# PGTN021_octasource2c_controls.net
KiCad netlist of a schematic drawn in EAGLE
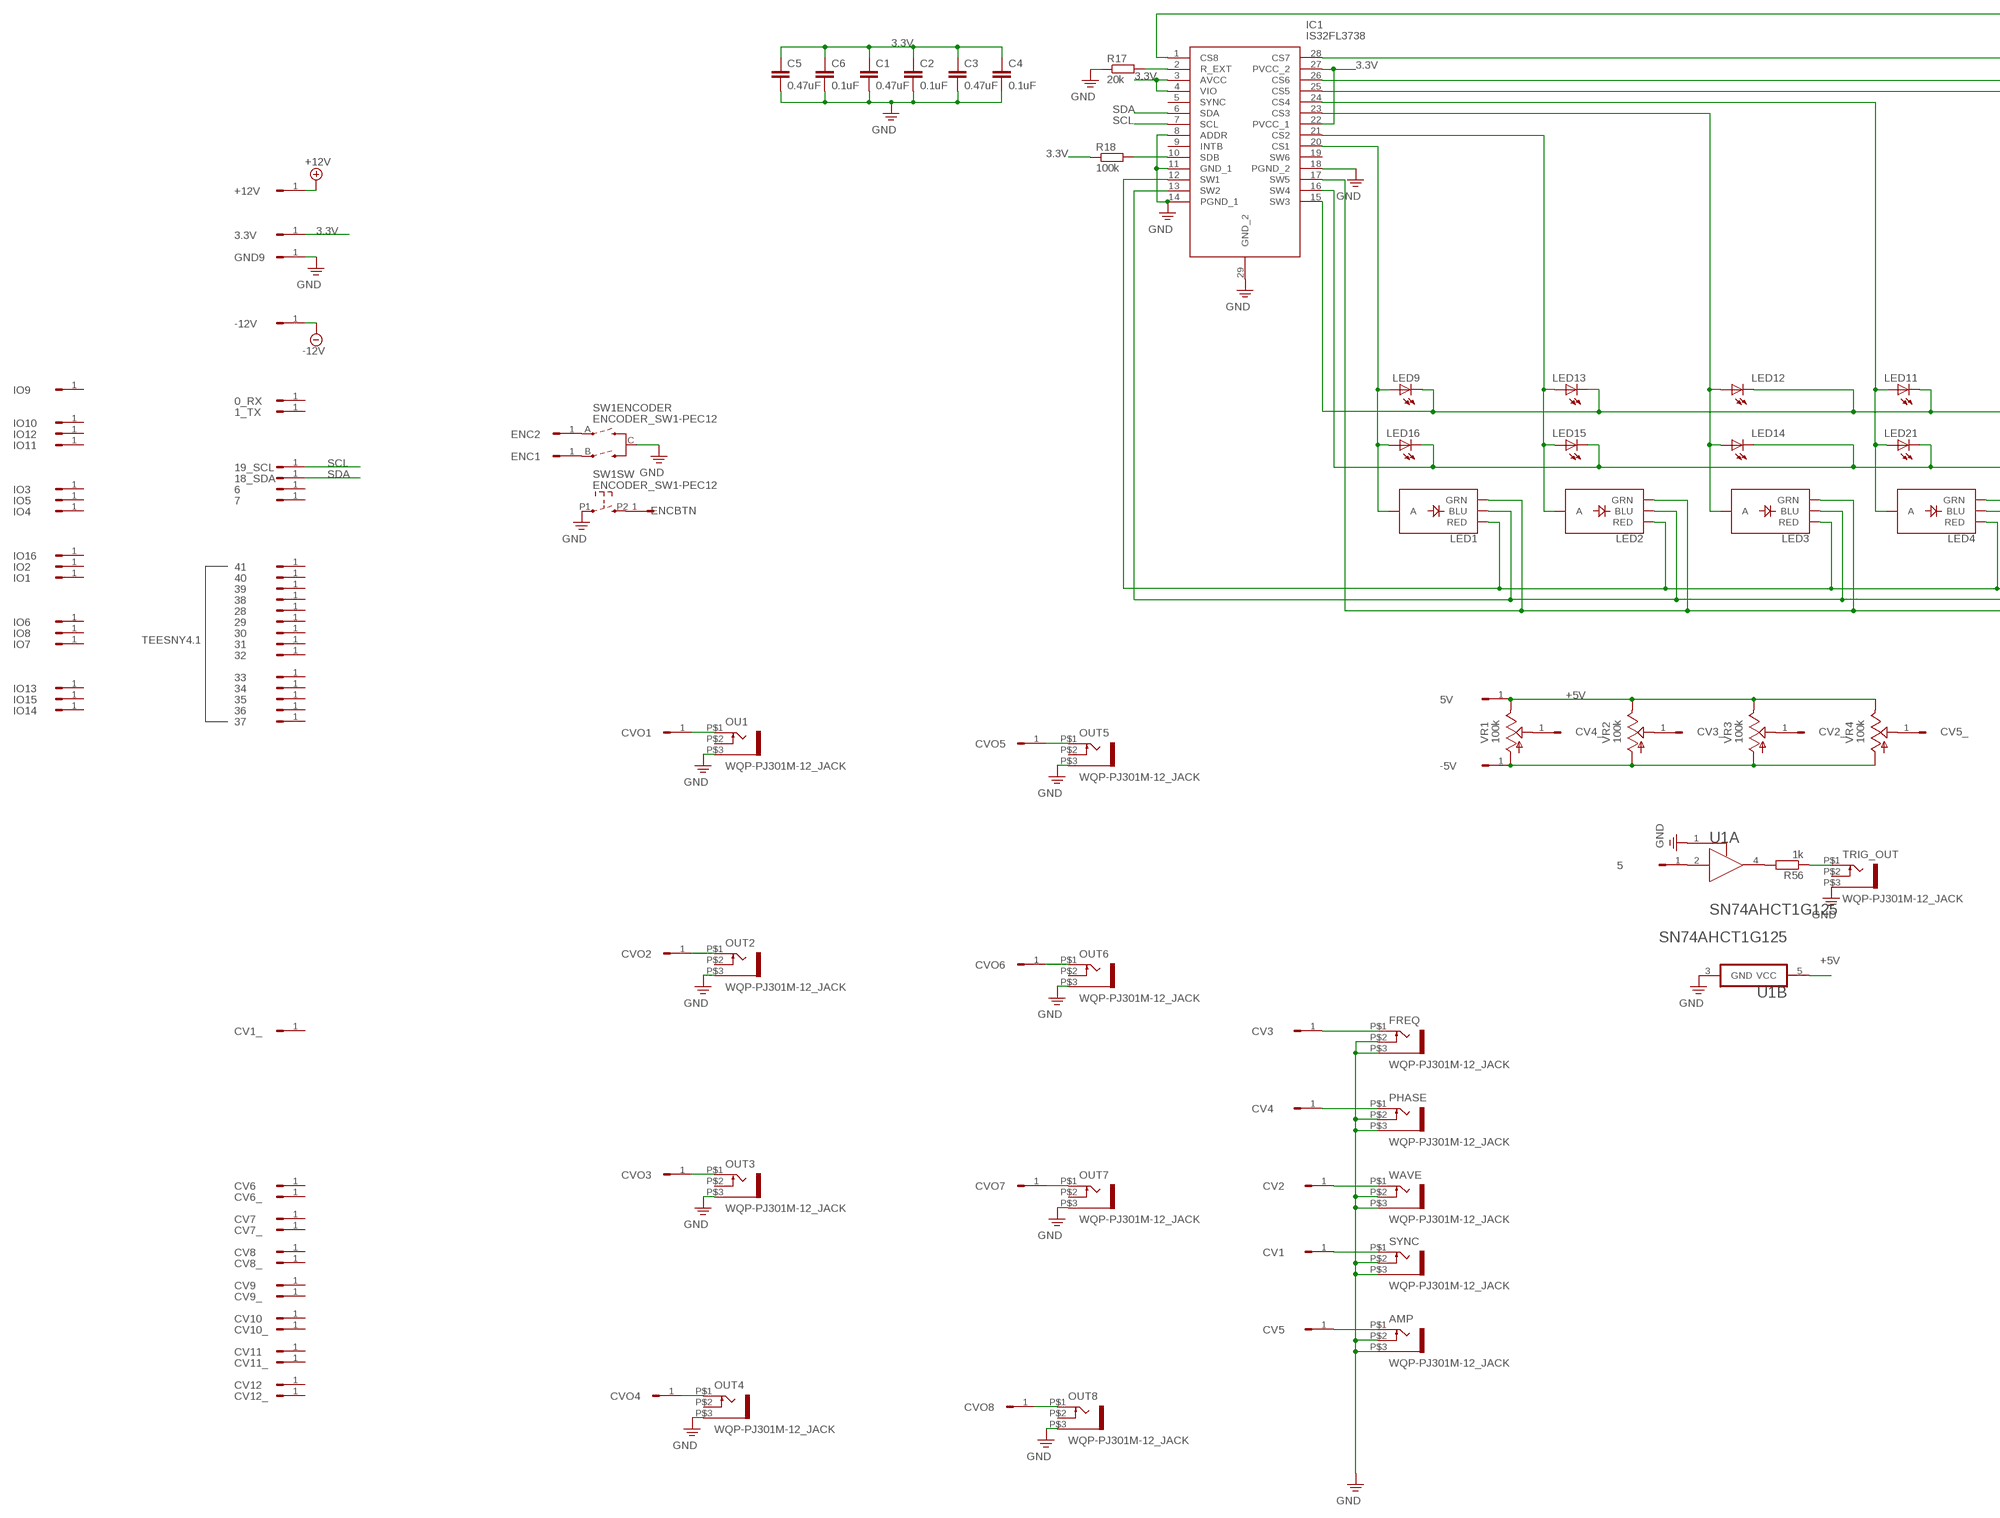
[diagram p0: schematic, sheet 1, part 1 of 2]
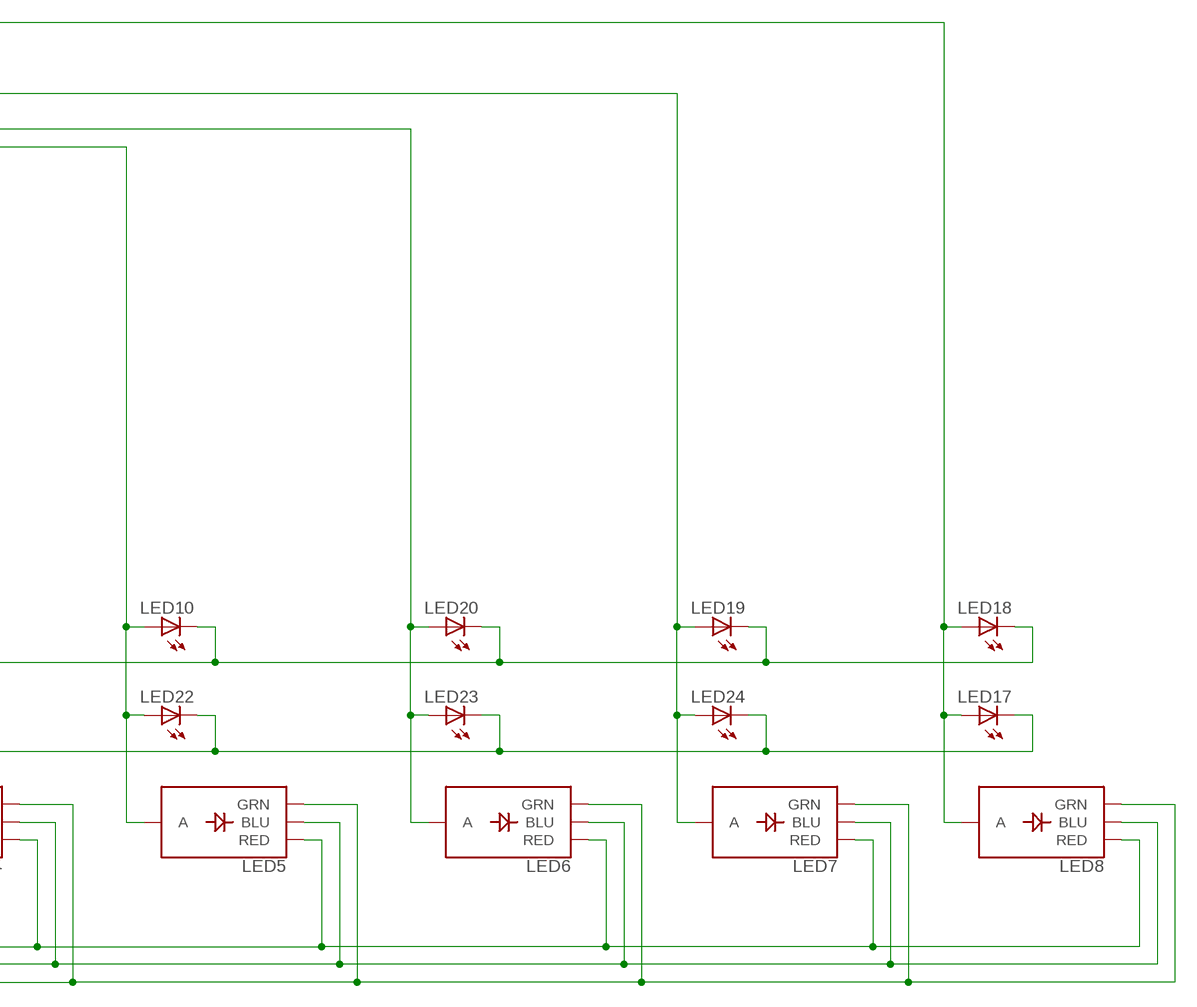
[diagram p1: schematic, sheet 1, part 2 of 2]

(export (version "E")
  (design (tool "Eeschema 10.0.6"))
  (components
    (comp (ref "+12V")
      (value "HEADER/MALE/01")
      (footprint "eagle-import:HEADER_MALE_01")
      (fields (field (name "SPICEPREFIX") "X"))
      (libsource (lib "eagle-import") (part "HEADER/MALE/01"))
    )
    (comp (ref "-5V")
      (value "HEADER/MALE/01")
      (footprint "eagle-import:HEADER_MALE_01")
      (fields (field (name "SPICEPREFIX") "X"))
      (libsource (lib "eagle-import") (part "HEADER/MALE/01"))
    )
    (comp (ref "-12V")
      (value "HEADER/MALE/01")
      (footprint "eagle-import:HEADER_MALE_01")
      (fields (field (name "SPICEPREFIX") "X"))
      (libsource (lib "eagle-import") (part "HEADER/MALE/01"))
    )
    (comp (ref "0_RX")
      (value "HEADER/MALE/01")
      (footprint "eagle-import:HEADER_MALE_01")
      (fields (field (name "SPICEPREFIX") "X"))
      (libsource (lib "eagle-import") (part "HEADER/MALE/01"))
    )
    (comp (ref "1_TX")
      (value "HEADER/MALE/01")
      (footprint "eagle-import:HEADER_MALE_01")
      (fields (field (name "SPICEPREFIX") "X"))
      (libsource (lib "eagle-import") (part "HEADER/MALE/01"))
    )
    (comp (ref "3.3V")
      (value "HEADER/MALE/01")
      (footprint "eagle-import:HEADER_MALE_01")
      (fields (field (name "SPICEPREFIX") "X"))
      (libsource (lib "eagle-import") (part "HEADER/MALE/01"))
    )
    (comp (ref "5")
      (value "HEADER/MALE/01")
      (footprint "eagle-import:HEADER_MALE_01")
      (fields (field (name "SPICEPREFIX") "X"))
      (libsource (lib "eagle-import") (part "HEADER/MALE/01"))
    )
    (comp (ref "5V")
      (value "HEADER/MALE/01")
      (footprint "eagle-import:HEADER_MALE_01")
      (fields (field (name "SPICEPREFIX") "X"))
      (libsource (lib "eagle-import") (part "HEADER/MALE/01"))
    )
    (comp (ref "6")
      (value "HEADER/MALE/01")
      (footprint "eagle-import:HEADER_MALE_01")
      (fields (field (name "SPICEPREFIX") "X"))
      (libsource (lib "eagle-import") (part "HEADER/MALE/01"))
    )
    (comp (ref "7")
      (value "HEADER/MALE/01")
      (footprint "eagle-import:HEADER_MALE_01")
      (fields (field (name "SPICEPREFIX") "X"))
      (libsource (lib "eagle-import") (part "HEADER/MALE/01"))
    )
    (comp (ref "18_SDA")
      (value "HEADER/MALE/01")
      (footprint "eagle-import:HEADER_MALE_01")
      (fields (field (name "SPICEPREFIX") "X"))
      (libsource (lib "eagle-import") (part "HEADER/MALE/01"))
    )
    (comp (ref "19_SCL")
      (value "HEADER/MALE/01")
      (footprint "eagle-import:HEADER_MALE_01")
      (fields (field (name "SPICEPREFIX") "X"))
      (libsource (lib "eagle-import") (part "HEADER/MALE/01"))
    )
    (comp (ref "28")
      (value "HEADER/MALE/01")
      (footprint "eagle-import:HEADER_MALE_01")
      (fields (field (name "SPICEPREFIX") "X"))
      (libsource (lib "eagle-import") (part "HEADER/MALE/01"))
    )
    (comp (ref "29")
      (value "HEADER/MALE/01")
      (footprint "eagle-import:HEADER_MALE_01")
      (fields (field (name "SPICEPREFIX") "X"))
      (libsource (lib "eagle-import") (part "HEADER/MALE/01"))
    )
    (comp (ref "30")
      (value "HEADER/MALE/01")
      (footprint "eagle-import:HEADER_MALE_01")
      (fields (field (name "SPICEPREFIX") "X"))
      (libsource (lib "eagle-import") (part "HEADER/MALE/01"))
    )
    (comp (ref "31")
      (value "HEADER/MALE/01")
      (footprint "eagle-import:HEADER_MALE_01")
      (fields (field (name "SPICEPREFIX") "X"))
      (libsource (lib "eagle-import") (part "HEADER/MALE/01"))
    )
    (comp (ref "32")
      (value "HEADER/MALE/01")
      (footprint "eagle-import:HEADER_MALE_01")
      (fields (field (name "SPICEPREFIX") "X"))
      (libsource (lib "eagle-import") (part "HEADER/MALE/01"))
    )
    (comp (ref "33")
      (value "HEADER/MALE/01")
      (footprint "eagle-import:HEADER_MALE_01")
      (fields (field (name "SPICEPREFIX") "X"))
      (libsource (lib "eagle-import") (part "HEADER/MALE/01"))
    )
    (comp (ref "34")
      (value "HEADER/MALE/01")
      (footprint "eagle-import:HEADER_MALE_01")
      (fields (field (name "SPICEPREFIX") "X"))
      (libsource (lib "eagle-import") (part "HEADER/MALE/01"))
    )
    (comp (ref "35")
      (value "HEADER/MALE/01")
      (footprint "eagle-import:HEADER_MALE_01")
      (fields (field (name "SPICEPREFIX") "X"))
      (libsource (lib "eagle-import") (part "HEADER/MALE/01"))
    )
    (comp (ref "36")
      (value "HEADER/MALE/01")
      (footprint "eagle-import:HEADER_MALE_01")
      (fields (field (name "SPICEPREFIX") "X"))
      (libsource (lib "eagle-import") (part "HEADER/MALE/01"))
    )
    (comp (ref "37")
      (value "HEADER/MALE/01")
      (footprint "eagle-import:HEADER_MALE_01")
      (fields (field (name "SPICEPREFIX") "X"))
      (libsource (lib "eagle-import") (part "HEADER/MALE/01"))
    )
    (comp (ref "38")
      (value "HEADER/MALE/01")
      (footprint "eagle-import:HEADER_MALE_01")
      (fields (field (name "SPICEPREFIX") "X"))
      (libsource (lib "eagle-import") (part "HEADER/MALE/01"))
    )
    (comp (ref "39")
      (value "HEADER/MALE/01")
      (footprint "eagle-import:HEADER_MALE_01")
      (fields (field (name "SPICEPREFIX") "X"))
      (libsource (lib "eagle-import") (part "HEADER/MALE/01"))
    )
    (comp (ref "40")
      (value "HEADER/MALE/01")
      (footprint "eagle-import:HEADER_MALE_01")
      (fields (field (name "SPICEPREFIX") "X"))
      (libsource (lib "eagle-import") (part "HEADER/MALE/01"))
    )
    (comp (ref "41")
      (value "HEADER/MALE/01")
      (footprint "eagle-import:HEADER_MALE_01")
      (fields (field (name "SPICEPREFIX") "X"))
      (libsource (lib "eagle-import") (part "HEADER/MALE/01"))
    )
    (comp (ref "AMP")
      (value "WQP-PJ301M-12_JACK")
      (footprint "eagle-import:WQP-PJ301M-12_JACK")
      (libsource (lib "eagle-import") (part "WQP-PJ301M-12_JACK"))
    )
    (comp (ref "C1")
      (value "0.47uF")
      (footprint "eagle-import:C0603")
      (libsource (lib "eagle-import") (part "CAPACITORC0603"))
    )
    (comp (ref "C2")
      (value "0.1uF")
      (footprint "eagle-import:C0603")
      (libsource (lib "eagle-import") (part "CAPACITORC0603"))
    )
    (comp (ref "C3")
      (value "0.47uF")
      (footprint "eagle-import:C0603")
      (libsource (lib "eagle-import") (part "CAPACITORC0603"))
    )
    (comp (ref "C4")
      (value "0.1uF")
      (footprint "eagle-import:C0603")
      (libsource (lib "eagle-import") (part "CAPACITORC0603"))
    )
    (comp (ref "C5")
      (value "0.47uF")
      (footprint "eagle-import:C0603")
      (libsource (lib "eagle-import") (part "CAPACITORC0603"))
    )
    (comp (ref "C6")
      (value "0.1uF")
      (footprint "eagle-import:C0603")
      (libsource (lib "eagle-import") (part "CAPACITORC0603"))
    )
    (comp (ref "CV1")
      (value "HEADER/MALE/01")
      (footprint "eagle-import:HEADER_MALE_01")
      (fields (field (name "SPICEPREFIX") "X"))
      (libsource (lib "eagle-import") (part "HEADER/MALE/01"))
    )
    (comp (ref "CV1_")
      (value "HEADER/MALE/01")
      (footprint "eagle-import:HEADER_MALE_01")
      (fields (field (name "SPICEPREFIX") "X"))
      (libsource (lib "eagle-import") (part "HEADER/MALE/01"))
    )
    (comp (ref "CV2")
      (value "HEADER/MALE/01")
      (footprint "eagle-import:HEADER_MALE_01")
      (fields (field (name "SPICEPREFIX") "X"))
      (libsource (lib "eagle-import") (part "HEADER/MALE/01"))
    )
    (comp (ref "CV2_")
      (value "HEADER/MALE/01")
      (footprint "eagle-import:HEADER_MALE_01")
      (fields (field (name "SPICEPREFIX") "X"))
      (libsource (lib "eagle-import") (part "HEADER/MALE/01"))
    )
    (comp (ref "CV3")
      (value "HEADER/MALE/01")
      (footprint "eagle-import:HEADER_MALE_01")
      (fields (field (name "SPICEPREFIX") "X"))
      (libsource (lib "eagle-import") (part "HEADER/MALE/01"))
    )
    (comp (ref "CV3_")
      (value "HEADER/MALE/01")
      (footprint "eagle-import:HEADER_MALE_01")
      (fields (field (name "SPICEPREFIX") "X"))
      (libsource (lib "eagle-import") (part "HEADER/MALE/01"))
    )
    (comp (ref "CV4")
      (value "HEADER/MALE/01")
      (footprint "eagle-import:HEADER_MALE_01")
      (fields (field (name "SPICEPREFIX") "X"))
      (libsource (lib "eagle-import") (part "HEADER/MALE/01"))
    )
    (comp (ref "CV4_")
      (value "HEADER/MALE/01")
      (footprint "eagle-import:HEADER_MALE_01")
      (fields (field (name "SPICEPREFIX") "X"))
      (libsource (lib "eagle-import") (part "HEADER/MALE/01"))
    )
    (comp (ref "CV5")
      (value "HEADER/MALE/01")
      (footprint "eagle-import:HEADER_MALE_01")
      (fields (field (name "SPICEPREFIX") "X"))
      (libsource (lib "eagle-import") (part "HEADER/MALE/01"))
    )
    (comp (ref "CV5_")
      (value "HEADER/MALE/01")
      (footprint "eagle-import:HEADER_MALE_01")
      (fields (field (name "SPICEPREFIX") "X"))
      (libsource (lib "eagle-import") (part "HEADER/MALE/01"))
    )
    (comp (ref "CV6")
      (value "HEADER/MALE/01")
      (footprint "eagle-import:HEADER_MALE_01")
      (fields (field (name "SPICEPREFIX") "X"))
      (libsource (lib "eagle-import") (part "HEADER/MALE/01"))
    )
    (comp (ref "CV6_")
      (value "HEADER/MALE/01")
      (footprint "eagle-import:HEADER_MALE_01")
      (fields (field (name "SPICEPREFIX") "X"))
      (libsource (lib "eagle-import") (part "HEADER/MALE/01"))
    )
    (comp (ref "CV7")
      (value "HEADER/MALE/01")
      (footprint "eagle-import:HEADER_MALE_01")
      (fields (field (name "SPICEPREFIX") "X"))
      (libsource (lib "eagle-import") (part "HEADER/MALE/01"))
    )
    (comp (ref "CV7_")
      (value "HEADER/MALE/01")
      (footprint "eagle-import:HEADER_MALE_01")
      (fields (field (name "SPICEPREFIX") "X"))
      (libsource (lib "eagle-import") (part "HEADER/MALE/01"))
    )
    (comp (ref "CV8")
      (value "HEADER/MALE/01")
      (footprint "eagle-import:HEADER_MALE_01")
      (fields (field (name "SPICEPREFIX") "X"))
      (libsource (lib "eagle-import") (part "HEADER/MALE/01"))
    )
    (comp (ref "CV8_")
      (value "HEADER/MALE/01")
      (footprint "eagle-import:HEADER_MALE_01")
      (fields (field (name "SPICEPREFIX") "X"))
      (libsource (lib "eagle-import") (part "HEADER/MALE/01"))
    )
    (comp (ref "CV9")
      (value "HEADER/MALE/01")
      (footprint "eagle-import:HEADER_MALE_01")
      (fields (field (name "SPICEPREFIX") "X"))
      (libsource (lib "eagle-import") (part "HEADER/MALE/01"))
    )
    (comp (ref "CV9_")
      (value "HEADER/MALE/01")
      (footprint "eagle-import:HEADER_MALE_01")
      (fields (field (name "SPICEPREFIX") "X"))
      (libsource (lib "eagle-import") (part "HEADER/MALE/01"))
    )
    (comp (ref "CV10")
      (value "HEADER/MALE/01")
      (footprint "eagle-import:HEADER_MALE_01")
      (fields (field (name "SPICEPREFIX") "X"))
      (libsource (lib "eagle-import") (part "HEADER/MALE/01"))
    )
    (comp (ref "CV10_")
      (value "HEADER/MALE/01")
      (footprint "eagle-import:HEADER_MALE_01")
      (fields (field (name "SPICEPREFIX") "X"))
      (libsource (lib "eagle-import") (part "HEADER/MALE/01"))
    )
    (comp (ref "CV11")
      (value "HEADER/MALE/01")
      (footprint "eagle-import:HEADER_MALE_01")
      (fields (field (name "SPICEPREFIX") "X"))
      (libsource (lib "eagle-import") (part "HEADER/MALE/01"))
    )
    (comp (ref "CV11_")
      (value "HEADER/MALE/01")
      (footprint "eagle-import:HEADER_MALE_01")
      (fields (field (name "SPICEPREFIX") "X"))
      (libsource (lib "eagle-import") (part "HEADER/MALE/01"))
    )
    (comp (ref "CV12")
      (value "HEADER/MALE/01")
      (footprint "eagle-import:HEADER_MALE_01")
      (fields (field (name "SPICEPREFIX") "X"))
      (libsource (lib "eagle-import") (part "HEADER/MALE/01"))
    )
    (comp (ref "CV12_")
      (value "HEADER/MALE/01")
      (footprint "eagle-import:HEADER_MALE_01")
      (fields (field (name "SPICEPREFIX") "X"))
      (libsource (lib "eagle-import") (part "HEADER/MALE/01"))
    )
    (comp (ref "CVO1")
      (value "HEADER/MALE/01")
      (footprint "eagle-import:HEADER_MALE_01")
      (fields (field (name "SPICEPREFIX") "X"))
      (libsource (lib "eagle-import") (part "HEADER/MALE/01"))
    )
    (comp (ref "CVO2")
      (value "HEADER/MALE/01")
      (footprint "eagle-import:HEADER_MALE_01")
      (fields (field (name "SPICEPREFIX") "X"))
      (libsource (lib "eagle-import") (part "HEADER/MALE/01"))
    )
    (comp (ref "CVO3")
      (value "HEADER/MALE/01")
      (footprint "eagle-import:HEADER_MALE_01")
      (fields (field (name "SPICEPREFIX") "X"))
      (libsource (lib "eagle-import") (part "HEADER/MALE/01"))
    )
    (comp (ref "CVO4")
      (value "HEADER/MALE/01")
      (footprint "eagle-import:HEADER_MALE_01")
      (fields (field (name "SPICEPREFIX") "X"))
      (libsource (lib "eagle-import") (part "HEADER/MALE/01"))
    )
    (comp (ref "CVO5")
      (value "HEADER/MALE/01")
      (footprint "eagle-import:HEADER_MALE_01")
      (fields (field (name "SPICEPREFIX") "X"))
      (libsource (lib "eagle-import") (part "HEADER/MALE/01"))
    )
    (comp (ref "CVO6")
      (value "HEADER/MALE/01")
      (footprint "eagle-import:HEADER_MALE_01")
      (fields (field (name "SPICEPREFIX") "X"))
      (libsource (lib "eagle-import") (part "HEADER/MALE/01"))
    )
    (comp (ref "CVO7")
      (value "HEADER/MALE/01")
      (footprint "eagle-import:HEADER_MALE_01")
      (fields (field (name "SPICEPREFIX") "X"))
      (libsource (lib "eagle-import") (part "HEADER/MALE/01"))
    )
    (comp (ref "CVO8")
      (value "HEADER/MALE/01")
      (footprint "eagle-import:HEADER_MALE_01")
      (fields (field (name "SPICEPREFIX") "X"))
      (libsource (lib "eagle-import") (part "HEADER/MALE/01"))
    )
    (comp (ref "ENC1")
      (value "HEADER/MALE/01")
      (footprint "eagle-import:HEADER_MALE_01")
      (fields (field (name "SPICEPREFIX") "X"))
      (libsource (lib "eagle-import") (part "HEADER/MALE/01"))
    )
    (comp (ref "ENC2")
      (value "HEADER/MALE/01")
      (footprint "eagle-import:HEADER_MALE_01")
      (fields (field (name "SPICEPREFIX") "X"))
      (libsource (lib "eagle-import") (part "HEADER/MALE/01"))
    )
    (comp (ref "ENCBTN")
      (value "HEADER/MALE/01")
      (footprint "eagle-import:HEADER_MALE_01")
      (fields (field (name "SPICEPREFIX") "X"))
      (libsource (lib "eagle-import") (part "HEADER/MALE/01"))
    )
    (comp (ref "FREQ")
      (value "WQP-PJ301M-12_JACK")
      (footprint "eagle-import:WQP-PJ301M-12_JACK")
      (libsource (lib "eagle-import") (part "WQP-PJ301M-12_JACK"))
    )
    (comp (ref "GND9")
      (value "HEADER/MALE/01")
      (footprint "eagle-import:HEADER_MALE_01")
      (fields (field (name "SPICEPREFIX") "X"))
      (libsource (lib "eagle-import") (part "HEADER/MALE/01"))
    )
    (comp (ref "IC1")
      (value "IS32FL3738")
      (footprint "eagle-import:TSSOP29")
      (fields (field (name "MANUFACTURER_PART_NUMBER") "IS32FL3738-ZLA3-TR"))
      (libsource (lib "eagle-import") (part "IS32FL3738"))
    )
    (comp (ref "IO1")
      (value "HEADER/MALE/01")
      (footprint "eagle-import:HEADER_MALE_01")
      (fields (field (name "SPICEPREFIX") "X"))
      (libsource (lib "eagle-import") (part "HEADER/MALE/01"))
    )
    (comp (ref "IO2")
      (value "HEADER/MALE/01")
      (footprint "eagle-import:HEADER_MALE_01")
      (fields (field (name "SPICEPREFIX") "X"))
      (libsource (lib "eagle-import") (part "HEADER/MALE/01"))
    )
    (comp (ref "IO3")
      (value "HEADER/MALE/01")
      (footprint "eagle-import:HEADER_MALE_01")
      (fields (field (name "SPICEPREFIX") "X"))
      (libsource (lib "eagle-import") (part "HEADER/MALE/01"))
    )
    (comp (ref "IO4")
      (value "HEADER/MALE/01")
      (footprint "eagle-import:HEADER_MALE_01")
      (fields (field (name "SPICEPREFIX") "X"))
      (libsource (lib "eagle-import") (part "HEADER/MALE/01"))
    )
    (comp (ref "IO5")
      (value "HEADER/MALE/01")
      (footprint "eagle-import:HEADER_MALE_01")
      (fields (field (name "SPICEPREFIX") "X"))
      (libsource (lib "eagle-import") (part "HEADER/MALE/01"))
    )
    (comp (ref "IO6")
      (value "HEADER/MALE/01")
      (footprint "eagle-import:HEADER_MALE_01")
      (fields (field (name "SPICEPREFIX") "X"))
      (libsource (lib "eagle-import") (part "HEADER/MALE/01"))
    )
    (comp (ref "IO7")
      (value "HEADER/MALE/01")
      (footprint "eagle-import:HEADER_MALE_01")
      (fields (field (name "SPICEPREFIX") "X"))
      (libsource (lib "eagle-import") (part "HEADER/MALE/01"))
    )
    (comp (ref "IO8")
      (value "HEADER/MALE/01")
      (footprint "eagle-import:HEADER_MALE_01")
      (fields (field (name "SPICEPREFIX") "X"))
      (libsource (lib "eagle-import") (part "HEADER/MALE/01"))
    )
    (comp (ref "IO9")
      (value "HEADER/MALE/01")
      (footprint "eagle-import:HEADER_MALE_01")
      (fields (field (name "SPICEPREFIX") "X"))
      (libsource (lib "eagle-import") (part "HEADER/MALE/01"))
    )
    (comp (ref "IO10")
      (value "HEADER/MALE/01")
      (footprint "eagle-import:HEADER_MALE_01")
      (fields (field (name "SPICEPREFIX") "X"))
      (libsource (lib "eagle-import") (part "HEADER/MALE/01"))
    )
    (comp (ref "IO11")
      (value "HEADER/MALE/01")
      (footprint "eagle-import:HEADER_MALE_01")
      (fields (field (name "SPICEPREFIX") "X"))
      (libsource (lib "eagle-import") (part "HEADER/MALE/01"))
    )
    (comp (ref "IO12")
      (value "HEADER/MALE/01")
      (footprint "eagle-import:HEADER_MALE_01")
      (fields (field (name "SPICEPREFIX") "X"))
      (libsource (lib "eagle-import") (part "HEADER/MALE/01"))
    )
    (comp (ref "IO13")
      (value "HEADER/MALE/01")
      (footprint "eagle-import:HEADER_MALE_01")
      (fields (field (name "SPICEPREFIX") "X"))
      (libsource (lib "eagle-import") (part "HEADER/MALE/01"))
    )
    (comp (ref "IO14")
      (value "HEADER/MALE/01")
      (footprint "eagle-import:HEADER_MALE_01")
      (fields (field (name "SPICEPREFIX") "X"))
      (libsource (lib "eagle-import") (part "HEADER/MALE/01"))
    )
    (comp (ref "IO15")
      (value "HEADER/MALE/01")
      (footprint "eagle-import:HEADER_MALE_01")
      (fields (field (name "SPICEPREFIX") "X"))
      (libsource (lib "eagle-import") (part "HEADER/MALE/01"))
    )
    (comp (ref "IO16")
      (value "HEADER/MALE/01")
      (footprint "eagle-import:HEADER_MALE_01")
      (fields (field (name "SPICEPREFIX") "X"))
      (libsource (lib "eagle-import") (part "HEADER/MALE/01"))
    )
    (comp (ref "LED1")
      (value "LED-RGB-CADIALIGHT1210")
      (footprint "eagle-import:CHIPLED_1210")
      (libsource (lib "eagle-import") (part "LED-RGB-CADIALIGHT1210"))
    )
    (comp (ref "LED2")
      (value "LED-RGB-CADIALIGHT1210")
      (footprint "eagle-import:CHIPLED_1210")
      (libsource (lib "eagle-import") (part "LED-RGB-CADIALIGHT1210"))
    )
    (comp (ref "LED3")
      (value "LED-RGB-CADIALIGHT1210")
      (footprint "eagle-import:CHIPLED_1210")
      (libsource (lib "eagle-import") (part "LED-RGB-CADIALIGHT1210"))
    )
    (comp (ref "LED4")
      (value "LED-RGB-CADIALIGHT1210")
      (footprint "eagle-import:CHIPLED_1210")
      (libsource (lib "eagle-import") (part "LED-RGB-CADIALIGHT1210"))
    )
    (comp (ref "LED5")
      (value "LED-RGB-CADIALIGHT1210")
      (footprint "eagle-import:CHIPLED_1210")
      (libsource (lib "eagle-import") (part "LED-RGB-CADIALIGHT1210"))
    )
    (comp (ref "LED6")
      (value "LED-RGB-CADIALIGHT1210")
      (footprint "eagle-import:CHIPLED_1210")
      (libsource (lib "eagle-import") (part "LED-RGB-CADIALIGHT1210"))
    )
    (comp (ref "LED7")
      (value "LED-RGB-CADIALIGHT1210")
      (footprint "eagle-import:CHIPLED_1210")
      (libsource (lib "eagle-import") (part "LED-RGB-CADIALIGHT1210"))
    )
    (comp (ref "LED8")
      (value "LED-RGB-CADIALIGHT1210")
      (footprint "eagle-import:CHIPLED_1210")
      (libsource (lib "eagle-import") (part "LED-RGB-CADIALIGHT1210"))
    )
    (comp (ref "LED9")
      (value "LEDCHIPLED_0805")
      (footprint "eagle-import:CHIPLED_0805")
      (libsource (lib "eagle-import") (part "LEDCHIPLED_0805"))
    )
    (comp (ref "LED10")
      (value "LEDCHIPLED_0805")
      (footprint "eagle-import:CHIPLED_0805")
      (libsource (lib "eagle-import") (part "LEDCHIPLED_0805"))
    )
    (comp (ref "LED11")
      (value "LEDCHIPLED_0805")
      (footprint "eagle-import:CHIPLED_0805")
      (libsource (lib "eagle-import") (part "LEDCHIPLED_0805"))
    )
    (comp (ref "LED12")
      (value "LEDCHIPLED_0805")
      (footprint "eagle-import:CHIPLED_0805")
      (libsource (lib "eagle-import") (part "LEDCHIPLED_0805"))
    )
    (comp (ref "LED13")
      (value "LEDCHIPLED_0805")
      (footprint "eagle-import:CHIPLED_0805")
      (libsource (lib "eagle-import") (part "LEDCHIPLED_0805"))
    )
    (comp (ref "LED14")
      (value "LEDCHIPLED_0805")
      (footprint "eagle-import:CHIPLED_0805")
      (libsource (lib "eagle-import") (part "LEDCHIPLED_0805"))
    )
    (comp (ref "LED15")
      (value "LEDCHIPLED_0805")
      (footprint "eagle-import:CHIPLED_0805")
      (libsource (lib "eagle-import") (part "LEDCHIPLED_0805"))
    )
    (comp (ref "LED16")
      (value "LEDCHIPLED_0805")
      (footprint "eagle-import:CHIPLED_0805")
      (libsource (lib "eagle-import") (part "LEDCHIPLED_0805"))
    )
    (comp (ref "LED17")
      (value "LEDCHIPLED_0805")
      (footprint "eagle-import:CHIPLED_0805")
      (libsource (lib "eagle-import") (part "LEDCHIPLED_0805"))
    )
    (comp (ref "LED18")
      (value "LEDCHIPLED_0805")
      (footprint "eagle-import:CHIPLED_0805")
      (libsource (lib "eagle-import") (part "LEDCHIPLED_0805"))
    )
    (comp (ref "LED19")
      (value "LEDCHIPLED_0805")
      (footprint "eagle-import:CHIPLED_0805")
      (libsource (lib "eagle-import") (part "LEDCHIPLED_0805"))
    )
    (comp (ref "LED20")
      (value "LEDCHIPLED_0805")
      (footprint "eagle-import:CHIPLED_0805")
      (libsource (lib "eagle-import") (part "LEDCHIPLED_0805"))
    )
    (comp (ref "LED21")
      (value "LEDCHIPLED_0805")
      (footprint "eagle-import:CHIPLED_0805")
      (libsource (lib "eagle-import") (part "LEDCHIPLED_0805"))
    )
    (comp (ref "LED22")
      (value "LEDCHIPLED_0805")
      (footprint "eagle-import:CHIPLED_0805")
      (libsource (lib "eagle-import") (part "LEDCHIPLED_0805"))
    )
    (comp (ref "LED23")
      (value "LEDCHIPLED_0805")
      (footprint "eagle-import:CHIPLED_0805")
      (libsource (lib "eagle-import") (part "LEDCHIPLED_0805"))
    )
    (comp (ref "LED24")
      (value "LEDCHIPLED_0805")
      (footprint "eagle-import:CHIPLED_0805")
      (libsource (lib "eagle-import") (part "LEDCHIPLED_0805"))
    )
    (comp (ref "OU1")
      (value "WQP-PJ301M-12_JACK")
      (footprint "eagle-import:WQP-PJ301M-12_JACK")
      (libsource (lib "eagle-import") (part "WQP-PJ301M-12_JACK"))
    )
    (comp (ref "OUT2")
      (value "WQP-PJ301M-12_JACK")
      (footprint "eagle-import:WQP-PJ301M-12_JACK")
      (libsource (lib "eagle-import") (part "WQP-PJ301M-12_JACK"))
    )
    (comp (ref "OUT3")
      (value "WQP-PJ301M-12_JACK")
      (footprint "eagle-import:WQP-PJ301M-12_JACK")
      (libsource (lib "eagle-import") (part "WQP-PJ301M-12_JACK"))
    )
    (comp (ref "OUT4")
      (value "WQP-PJ301M-12_JACK")
      (footprint "eagle-import:WQP-PJ301M-12_JACK")
      (libsource (lib "eagle-import") (part "WQP-PJ301M-12_JACK"))
    )
    (comp (ref "OUT5")
      (value "WQP-PJ301M-12_JACK")
      (footprint "eagle-import:WQP-PJ301M-12_JACK")
      (libsource (lib "eagle-import") (part "WQP-PJ301M-12_JACK"))
    )
    (comp (ref "OUT6")
      (value "WQP-PJ301M-12_JACK")
      (footprint "eagle-import:WQP-PJ301M-12_JACK")
      (libsource (lib "eagle-import") (part "WQP-PJ301M-12_JACK"))
    )
    (comp (ref "OUT7")
      (value "WQP-PJ301M-12_JACK")
      (footprint "eagle-import:WQP-PJ301M-12_JACK")
      (libsource (lib "eagle-import") (part "WQP-PJ301M-12_JACK"))
    )
    (comp (ref "OUT8")
      (value "WQP-PJ301M-12_JACK")
      (footprint "eagle-import:WQP-PJ301M-12_JACK")
      (libsource (lib "eagle-import") (part "WQP-PJ301M-12_JACK"))
    )
    (comp (ref "PHASE")
      (value "WQP-PJ301M-12_JACK")
      (footprint "eagle-import:WQP-PJ301M-12_JACK")
      (libsource (lib "eagle-import") (part "WQP-PJ301M-12_JACK"))
    )
    (comp (ref "R17")
      (value "20k")
      (footprint "eagle-import:R0603")
      (libsource (lib "eagle-import") (part "RESISTOR"))
    )
    (comp (ref "R18")
      (value "100k")
      (footprint "eagle-import:R0603")
      (libsource (lib "eagle-import") (part "RESISTOR"))
    )
    (comp (ref "R56")
      (value "1k")
      (footprint "eagle-import:R0603")
      (libsource (lib "eagle-import") (part "RESISTOR"))
    )
    (comp (ref "SW1")
      (value "ENCODER_SW1-PEC12")
      (footprint "eagle-import:PEC12_INCREMENTAL_ENCODER")
      (libsource (lib "eagle-import") (part "ENCODER_SW1-PEC12"))
    )
    (comp (ref "SYNC")
      (value "WQP-PJ301M-12_JACK")
      (footprint "eagle-import:WQP-PJ301M-12_JACK")
      (libsource (lib "eagle-import") (part "WQP-PJ301M-12_JACK"))
    )
    (comp (ref "TRIG_OUT")
      (value "WQP-PJ301M-12_JACK")
      (footprint "eagle-import:WQP-PJ301M-12_JACK")
      (libsource (lib "eagle-import") (part "WQP-PJ301M-12_JACK"))
    )
    (comp (ref "U1")
      (value "74AHCT1G125\"")
      (footprint "eagle-import:74AHCT1G125")
      (fields (field (name "MF") "Texas Instruments") (field (name "MPN") "SN74AHCT1G125"))
      (libsource (lib "eagle-import") (part "74AHCT1G125{dblquote}"))
    )
    (comp (ref "VR1")
      (value "100k")
      (footprint "eagle-import:9MM_SNAP-IN_POT")
      (libsource (lib "eagle-import") (part "9MM_SNAP-IN_POT_"))
    )
    (comp (ref "VR2")
      (value "100k")
      (footprint "eagle-import:9MM_SNAP-IN_POT")
      (libsource (lib "eagle-import") (part "9MM_SNAP-IN_POT_"))
    )
    (comp (ref "VR3")
      (value "100k")
      (footprint "eagle-import:9MM_SNAP-IN_POT")
      (libsource (lib "eagle-import") (part "9MM_SNAP-IN_POT_"))
    )
    (comp (ref "VR4")
      (value "100k")
      (footprint "eagle-import:9MM_SNAP-IN_POT")
      (libsource (lib "eagle-import") (part "9MM_SNAP-IN_POT_"))
    )
    (comp (ref "WAVE")
      (value "WQP-PJ301M-12_JACK")
      (footprint "eagle-import:WQP-PJ301M-12_JACK")
      (libsource (lib "eagle-import") (part "WQP-PJ301M-12_JACK"))
    )
  )
  (nets
    (net (code "1") (name "+12V") (class "Default")
      (node (ref "+12V") (pin "1") (pinfunction "3_1") (pintype "passive"))
    )
    (net (code "2") (name "-12V") (class "Default")
      (node (ref "-12V") (pin "1") (pinfunction "3_1") (pintype "passive"))
    )
    (net (code "3") (name "/+5V") (class "Default")
      (node (ref "5V") (pin "1") (pinfunction "3_1") (pintype "passive"))
      (node (ref "U1") (pin "5") (pinfunction "VCC_5") (pintype "power_in"))
      (node (ref "VR1") (pin "3") (pinfunction "E_3") (pintype "passive"))
      (node (ref "VR2") (pin "3") (pinfunction "E_3") (pintype "passive"))
      (node (ref "VR3") (pin "3") (pinfunction "E_3") (pintype "passive"))
      (node (ref "VR4") (pin "3") (pinfunction "E_3") (pintype "passive"))
    )
    (net (code "4") (name "/3.3V") (class "Default")
      (node (ref "3.3V") (pin "1") (pinfunction "3_1") (pintype "passive"))
      (node (ref "C1") (pin "1") (pinfunction "1_1") (pintype "passive"))
      (node (ref "C2") (pin "1") (pinfunction "1_1") (pintype "passive"))
      (node (ref "C3") (pin "1") (pinfunction "1_1") (pintype "passive"))
      (node (ref "C4") (pin "1") (pinfunction "1_1") (pintype "passive"))
      (node (ref "C5") (pin "1") (pinfunction "1_1") (pintype "passive"))
      (node (ref "C6") (pin "1") (pinfunction "1_1") (pintype "passive"))
      (node (ref "IC1") (pin "22") (pinfunction "PVCC_1_22") (pintype "power_in"))
      (node (ref "IC1") (pin "27") (pinfunction "PVCC_2_27") (pintype "power_in"))
      (node (ref "IC1") (pin "3") (pinfunction "AVCC_3") (pintype "power_in"))
      (node (ref "IC1") (pin "4") (pinfunction "VIO_4") (pintype "input"))
      (node (ref "R18") (pin "1") (pinfunction "1_1") (pintype "passive"))
    )
    (net (code "5") (name "/SCL") (class "Default")
      (node (ref "19_SCL") (pin "1") (pinfunction "3_1") (pintype "passive"))
      (node (ref "IC1") (pin "7") (pinfunction "SCL_7") (pintype "bidirectional"))
    )
    (net (code "6") (name "/SDA") (class "Default")
      (node (ref "18_SDA") (pin "1") (pinfunction "3_1") (pintype "passive"))
      (node (ref "IC1") (pin "6") (pinfunction "SDA_6") (pintype "bidirectional"))
    )
    (net (code "7") (name "GND") (class "Default")
      (node (ref "AMP") (pin "P$2") (pinfunction "3_P$2") (pintype "passive"))
      (node (ref "AMP") (pin "P$3") (pinfunction "1_P$3") (pintype "passive"))
      (node (ref "C1") (pin "2") (pinfunction "2_2") (pintype "passive"))
      (node (ref "C2") (pin "2") (pinfunction "2_2") (pintype "passive"))
      (node (ref "C3") (pin "2") (pinfunction "2_2") (pintype "passive"))
      (node (ref "C4") (pin "2") (pinfunction "2_2") (pintype "passive"))
      (node (ref "C5") (pin "2") (pinfunction "2_2") (pintype "passive"))
      (node (ref "C6") (pin "2") (pinfunction "2_2") (pintype "passive"))
      (node (ref "FREQ") (pin "P$2") (pinfunction "3_P$2") (pintype "passive"))
      (node (ref "FREQ") (pin "P$3") (pinfunction "1_P$3") (pintype "passive"))
      (node (ref "GND9") (pin "1") (pinfunction "3_1") (pintype "passive"))
      (node (ref "IC1") (pin "11") (pinfunction "GND_1_11") (pintype "power_in"))
      (node (ref "IC1") (pin "14") (pinfunction "PGND_1_14") (pintype "power_in"))
      (node (ref "IC1") (pin "18") (pinfunction "PGND_2_18") (pintype "power_in"))
      (node (ref "IC1") (pin "29") (pinfunction "GND_2_29") (pintype "power_in"))
      (node (ref "IC1") (pin "8") (pinfunction "ADDR_8") (pintype "input"))
      (node (ref "OU1") (pin "P$3") (pinfunction "1_P$3") (pintype "passive"))
      (node (ref "OUT2") (pin "P$3") (pinfunction "1_P$3") (pintype "passive"))
      (node (ref "OUT3") (pin "P$3") (pinfunction "1_P$3") (pintype "passive"))
      (node (ref "OUT4") (pin "P$3") (pinfunction "1_P$3") (pintype "passive"))
      (node (ref "OUT5") (pin "P$3") (pinfunction "1_P$3") (pintype "passive"))
      (node (ref "OUT6") (pin "P$3") (pinfunction "1_P$3") (pintype "passive"))
      (node (ref "OUT7") (pin "P$3") (pinfunction "1_P$3") (pintype "passive"))
      (node (ref "OUT8") (pin "P$3") (pinfunction "1_P$3") (pintype "passive"))
      (node (ref "PHASE") (pin "P$2") (pinfunction "3_P$2") (pintype "passive"))
      (node (ref "PHASE") (pin "P$3") (pinfunction "1_P$3") (pintype "passive"))
      (node (ref "R17") (pin "1") (pinfunction "1_1") (pintype "passive"))
      (node (ref "SW1") (pin "C") (pinfunction "C_C") (pintype "passive"))
      (node (ref "SW1") (pin "P1") (pinfunction "1_P1") (pintype "passive"))
      (node (ref "SYNC") (pin "P$2") (pinfunction "3_P$2") (pintype "passive"))
      (node (ref "SYNC") (pin "P$3") (pinfunction "1_P$3") (pintype "passive"))
      (node (ref "TRIG_OUT") (pin "P$3") (pinfunction "1_P$3") (pintype "passive"))
      (node (ref "U1") (pin "1") (pinfunction "~{OE}_1") (pintype "input"))
      (node (ref "U1") (pin "3") (pinfunction "GND_3") (pintype "power_in"))
      (node (ref "WAVE") (pin "P$2") (pinfunction "3_P$2") (pintype "passive"))
      (node (ref "WAVE") (pin "P$3") (pinfunction "1_P$3") (pintype "passive"))
    )
    (net (code "8") (name "Net-(-5V-3)") (class "Default")
      (node (ref "-5V") (pin "1") (pinfunction "3_1") (pintype "passive"))
      (node (ref "VR1") (pin "1") (pinfunction "A_1") (pintype "passive"))
      (node (ref "VR2") (pin "1") (pinfunction "A_1") (pintype "passive"))
      (node (ref "VR3") (pin "1") (pinfunction "A_1") (pintype "passive"))
      (node (ref "VR4") (pin "1") (pinfunction "A_1") (pintype "passive"))
    )
    (net (code "9") (name "Net-(5-3)") (class "Default")
      (node (ref "5") (pin "1") (pinfunction "3_1") (pintype "passive"))
      (node (ref "U1") (pin "2") (pinfunction "A_2") (pintype "input"))
    )
    (net (code "10") (name "Net-(AMP-2)") (class "Default")
      (node (ref "AMP") (pin "P$1") (pinfunction "2_P$1") (pintype "passive"))
      (node (ref "CV5") (pin "1") (pinfunction "3_1") (pintype "passive"))
    )
    (net (code "11") (name "Net-(CV1-3)") (class "Default")
      (node (ref "CV1") (pin "1") (pinfunction "3_1") (pintype "passive"))
      (node (ref "SYNC") (pin "P$1") (pinfunction "2_P$1") (pintype "passive"))
    )
    (net (code "12") (name "Net-(CV2-3)") (class "Default")
      (node (ref "CV2") (pin "1") (pinfunction "3_1") (pintype "passive"))
      (node (ref "WAVE") (pin "P$1") (pinfunction "2_P$1") (pintype "passive"))
    )
    (net (code "13") (name "Net-(CV2_-3)") (class "Default")
      (node (ref "CV2_") (pin "1") (pinfunction "3_1") (pintype "passive"))
      (node (ref "VR3") (pin "2") (pinfunction "S_2") (pintype "passive"))
    )
    (net (code "14") (name "Net-(CV3-3)") (class "Default")
      (node (ref "CV3") (pin "1") (pinfunction "3_1") (pintype "passive"))
      (node (ref "FREQ") (pin "P$1") (pinfunction "2_P$1") (pintype "passive"))
    )
    (net (code "15") (name "Net-(CV3_-3)") (class "Default")
      (node (ref "CV3_") (pin "1") (pinfunction "3_1") (pintype "passive"))
      (node (ref "VR2") (pin "2") (pinfunction "S_2") (pintype "passive"))
    )
    (net (code "16") (name "Net-(CV4-3)") (class "Default")
      (node (ref "CV4") (pin "1") (pinfunction "3_1") (pintype "passive"))
      (node (ref "PHASE") (pin "P$1") (pinfunction "2_P$1") (pintype "passive"))
    )
    (net (code "17") (name "Net-(CV4_-3)") (class "Default")
      (node (ref "CV4_") (pin "1") (pinfunction "3_1") (pintype "passive"))
      (node (ref "VR1") (pin "2") (pinfunction "S_2") (pintype "passive"))
    )
    (net (code "18") (name "Net-(CV5_-3)") (class "Default")
      (node (ref "CV5_") (pin "1") (pinfunction "3_1") (pintype "passive"))
      (node (ref "VR4") (pin "2") (pinfunction "S_2") (pintype "passive"))
    )
    (net (code "19") (name "Net-(CVO1-3)") (class "Default")
      (node (ref "CVO1") (pin "1") (pinfunction "3_1") (pintype "passive"))
      (node (ref "OU1") (pin "P$1") (pinfunction "2_P$1") (pintype "passive"))
    )
    (net (code "20") (name "Net-(CVO2-3)") (class "Default")
      (node (ref "CVO2") (pin "1") (pinfunction "3_1") (pintype "passive"))
      (node (ref "OUT2") (pin "P$1") (pinfunction "2_P$1") (pintype "passive"))
    )
    (net (code "21") (name "Net-(CVO3-3)") (class "Default")
      (node (ref "CVO3") (pin "1") (pinfunction "3_1") (pintype "passive"))
      (node (ref "OUT3") (pin "P$1") (pinfunction "2_P$1") (pintype "passive"))
    )
    (net (code "22") (name "Net-(CVO4-3)") (class "Default")
      (node (ref "CVO4") (pin "1") (pinfunction "3_1") (pintype "passive"))
      (node (ref "OUT4") (pin "P$1") (pinfunction "2_P$1") (pintype "passive"))
    )
    (net (code "23") (name "Net-(CVO5-3)") (class "Default")
      (node (ref "CVO5") (pin "1") (pinfunction "3_1") (pintype "passive"))
      (node (ref "OUT5") (pin "P$1") (pinfunction "2_P$1") (pintype "passive"))
    )
    (net (code "24") (name "Net-(CVO6-3)") (class "Default")
      (node (ref "CVO6") (pin "1") (pinfunction "3_1") (pintype "passive"))
      (node (ref "OUT6") (pin "P$1") (pinfunction "2_P$1") (pintype "passive"))
    )
    (net (code "25") (name "Net-(CVO7-3)") (class "Default")
      (node (ref "CVO7") (pin "1") (pinfunction "3_1") (pintype "passive"))
      (node (ref "OUT7") (pin "P$1") (pinfunction "2_P$1") (pintype "passive"))
    )
    (net (code "26") (name "Net-(CVO8-3)") (class "Default")
      (node (ref "CVO8") (pin "1") (pinfunction "3_1") (pintype "passive"))
      (node (ref "OUT8") (pin "P$1") (pinfunction "2_P$1") (pintype "passive"))
    )
    (net (code "27") (name "Net-(ENC1-3)") (class "Default")
      (node (ref "ENC1") (pin "1") (pinfunction "3_1") (pintype "passive"))
      (node (ref "SW1") (pin "B") (pinfunction "B_B") (pintype "passive"))
    )
    (net (code "28") (name "Net-(ENC2-3)") (class "Default")
      (node (ref "ENC2") (pin "1") (pinfunction "3_1") (pintype "passive"))
      (node (ref "SW1") (pin "A") (pinfunction "A_A") (pintype "passive"))
    )
    (net (code "29") (name "Net-(ENCBTN-3)") (class "Default")
      (node (ref "ENCBTN") (pin "1") (pinfunction "3_1") (pintype "passive"))
      (node (ref "SW1") (pin "P2") (pinfunction "2_P2") (pintype "passive"))
    )
    (net (code "30") (name "Net-(IC1-CS1)") (class "Default")
      (node (ref "IC1") (pin "20") (pinfunction "CS1_20") (pintype "output"))
      (node (ref "LED1") (pin "4") (pinfunction "A_4") (pintype "bidirectional"))
      (node (ref "LED16") (pin "A") (pinfunction "A_A") (pintype "passive"))
      (node (ref "LED9") (pin "A") (pinfunction "A_A") (pintype "passive"))
    )
    (net (code "31") (name "Net-(IC1-CS2)") (class "Default")
      (node (ref "IC1") (pin "21") (pinfunction "CS2_21") (pintype "output"))
      (node (ref "LED13") (pin "A") (pinfunction "A_A") (pintype "passive"))
      (node (ref "LED15") (pin "A") (pinfunction "A_A") (pintype "passive"))
      (node (ref "LED2") (pin "4") (pinfunction "A_4") (pintype "bidirectional"))
    )
    (net (code "32") (name "Net-(IC1-CS3)") (class "Default")
      (node (ref "IC1") (pin "23") (pinfunction "CS3_23") (pintype "bidirectional"))
      (node (ref "LED12") (pin "A") (pinfunction "A_A") (pintype "passive"))
      (node (ref "LED14") (pin "A") (pinfunction "A_A") (pintype "passive"))
      (node (ref "LED3") (pin "4") (pinfunction "A_4") (pintype "bidirectional"))
    )
    (net (code "33") (name "Net-(IC1-CS4)") (class "Default")
      (node (ref "IC1") (pin "24") (pinfunction "CS4_24") (pintype "bidirectional"))
      (node (ref "LED11") (pin "A") (pinfunction "A_A") (pintype "passive"))
      (node (ref "LED21") (pin "A") (pinfunction "A_A") (pintype "passive"))
      (node (ref "LED4") (pin "4") (pinfunction "A_4") (pintype "bidirectional"))
    )
    (net (code "34") (name "Net-(IC1-CS5)") (class "Default")
      (node (ref "IC1") (pin "25") (pinfunction "CS5_25") (pintype "bidirectional"))
      (node (ref "LED10") (pin "A") (pinfunction "A_A") (pintype "passive"))
      (node (ref "LED22") (pin "A") (pinfunction "A_A") (pintype "passive"))
      (node (ref "LED5") (pin "4") (pinfunction "A_4") (pintype "bidirectional"))
    )
    (net (code "35") (name "Net-(IC1-CS6)") (class "Default")
      (node (ref "IC1") (pin "26") (pinfunction "CS6_26") (pintype "bidirectional"))
      (node (ref "LED20") (pin "A") (pinfunction "A_A") (pintype "passive"))
      (node (ref "LED23") (pin "A") (pinfunction "A_A") (pintype "passive"))
      (node (ref "LED6") (pin "4") (pinfunction "A_4") (pintype "bidirectional"))
    )
    (net (code "36") (name "Net-(IC1-CS7)") (class "Default")
      (node (ref "IC1") (pin "28") (pinfunction "CS7_28") (pintype "output"))
      (node (ref "LED19") (pin "A") (pinfunction "A_A") (pintype "passive"))
      (node (ref "LED24") (pin "A") (pinfunction "A_A") (pintype "passive"))
      (node (ref "LED7") (pin "4") (pinfunction "A_4") (pintype "bidirectional"))
    )
    (net (code "37") (name "Net-(IC1-CS8)") (class "Default")
      (node (ref "IC1") (pin "1") (pinfunction "CS8_1") (pintype "output"))
      (node (ref "LED17") (pin "A") (pinfunction "A_A") (pintype "passive"))
      (node (ref "LED18") (pin "A") (pinfunction "A_A") (pintype "passive"))
      (node (ref "LED8") (pin "4") (pinfunction "A_4") (pintype "bidirectional"))
    )
    (net (code "38") (name "Net-(IC1-R_EXT)") (class "Default")
      (node (ref "IC1") (pin "2") (pinfunction "R_EXT_2") (pintype "input"))
      (node (ref "R17") (pin "2") (pinfunction "2_2") (pintype "passive"))
    )
    (net (code "39") (name "Net-(IC1-SDB)") (class "Default")
      (node (ref "IC1") (pin "10") (pinfunction "SDB_10") (pintype "input"))
      (node (ref "R18") (pin "2") (pinfunction "2_2") (pintype "passive"))
    )
    (net (code "40") (name "Net-(IC1-SW1)") (class "Default")
      (node (ref "IC1") (pin "12") (pinfunction "SW1_12") (pintype "output"))
      (node (ref "LED1") (pin "2") (pinfunction "RED_2") (pintype "bidirectional"))
      (node (ref "LED2") (pin "2") (pinfunction "RED_2") (pintype "bidirectional"))
      (node (ref "LED3") (pin "2") (pinfunction "RED_2") (pintype "bidirectional"))
      (node (ref "LED4") (pin "2") (pinfunction "RED_2") (pintype "bidirectional"))
      (node (ref "LED5") (pin "2") (pinfunction "RED_2") (pintype "bidirectional"))
      (node (ref "LED6") (pin "2") (pinfunction "RED_2") (pintype "bidirectional"))
      (node (ref "LED7") (pin "2") (pinfunction "RED_2") (pintype "bidirectional"))
      (node (ref "LED8") (pin "2") (pinfunction "RED_2") (pintype "bidirectional"))
    )
    (net (code "41") (name "Net-(IC1-SW2)") (class "Default")
      (node (ref "IC1") (pin "13") (pinfunction "SW2_13") (pintype "output"))
      (node (ref "LED1") (pin "1") (pinfunction "BLU_1") (pintype "bidirectional"))
      (node (ref "LED2") (pin "1") (pinfunction "BLU_1") (pintype "bidirectional"))
      (node (ref "LED3") (pin "1") (pinfunction "BLU_1") (pintype "bidirectional"))
      (node (ref "LED4") (pin "1") (pinfunction "BLU_1") (pintype "bidirectional"))
      (node (ref "LED5") (pin "1") (pinfunction "BLU_1") (pintype "bidirectional"))
      (node (ref "LED6") (pin "1") (pinfunction "BLU_1") (pintype "bidirectional"))
      (node (ref "LED7") (pin "1") (pinfunction "BLU_1") (pintype "bidirectional"))
      (node (ref "LED8") (pin "1") (pinfunction "BLU_1") (pintype "bidirectional"))
    )
    (net (code "42") (name "Net-(IC1-SW3)") (class "Default")
      (node (ref "IC1") (pin "15") (pinfunction "SW3_15") (pintype "output"))
      (node (ref "LED10") (pin "C") (pinfunction "C_C") (pintype "passive"))
      (node (ref "LED11") (pin "C") (pinfunction "C_C") (pintype "passive"))
      (node (ref "LED12") (pin "C") (pinfunction "C_C") (pintype "passive"))
      (node (ref "LED13") (pin "C") (pinfunction "C_C") (pintype "passive"))
      (node (ref "LED18") (pin "C") (pinfunction "C_C") (pintype "passive"))
      (node (ref "LED19") (pin "C") (pinfunction "C_C") (pintype "passive"))
      (node (ref "LED20") (pin "C") (pinfunction "C_C") (pintype "passive"))
      (node (ref "LED9") (pin "C") (pinfunction "C_C") (pintype "passive"))
    )
    (net (code "43") (name "Net-(IC1-SW4)") (class "Default")
      (node (ref "IC1") (pin "16") (pinfunction "SW4_16") (pintype "output"))
      (node (ref "LED14") (pin "C") (pinfunction "C_C") (pintype "passive"))
      (node (ref "LED15") (pin "C") (pinfunction "C_C") (pintype "passive"))
      (node (ref "LED16") (pin "C") (pinfunction "C_C") (pintype "passive"))
      (node (ref "LED17") (pin "C") (pinfunction "C_C") (pintype "passive"))
      (node (ref "LED21") (pin "C") (pinfunction "C_C") (pintype "passive"))
      (node (ref "LED22") (pin "C") (pinfunction "C_C") (pintype "passive"))
      (node (ref "LED23") (pin "C") (pinfunction "C_C") (pintype "passive"))
      (node (ref "LED24") (pin "C") (pinfunction "C_C") (pintype "passive"))
    )
    (net (code "44") (name "Net-(IC1-SW5)") (class "Default")
      (node (ref "IC1") (pin "17") (pinfunction "SW5_17") (pintype "output"))
      (node (ref "LED1") (pin "3") (pinfunction "GRN_3") (pintype "bidirectional"))
      (node (ref "LED2") (pin "3") (pinfunction "GRN_3") (pintype "bidirectional"))
      (node (ref "LED3") (pin "3") (pinfunction "GRN_3") (pintype "bidirectional"))
      (node (ref "LED4") (pin "3") (pinfunction "GRN_3") (pintype "bidirectional"))
      (node (ref "LED5") (pin "3") (pinfunction "GRN_3") (pintype "bidirectional"))
      (node (ref "LED6") (pin "3") (pinfunction "GRN_3") (pintype "bidirectional"))
      (node (ref "LED7") (pin "3") (pinfunction "GRN_3") (pintype "bidirectional"))
      (node (ref "LED8") (pin "3") (pinfunction "GRN_3") (pintype "bidirectional"))
    )
    (net (code "45") (name "Net-(TRIG_OUT-2)") (class "Default")
      (node (ref "R56") (pin "1") (pinfunction "1_1") (pintype "passive"))
      (node (ref "TRIG_OUT") (pin "P$1") (pinfunction "2_P$1") (pintype "passive"))
    )
    (net (code "46") (name "Net-(U1A-Y)") (class "Default")
      (node (ref "R56") (pin "2") (pinfunction "2_2") (pintype "passive"))
      (node (ref "U1") (pin "4") (pinfunction "Y_4") (pintype "tri_state"))
    )
    (net (code "47") (name "unconnected-(0_RX-3-Pad1)") (class "Default")
      (node (ref "0_RX") (pin "1") (pinfunction "3_1") (pintype "passive"))
    )
    (net (code "48") (name "unconnected-(1_TX-3-Pad1)") (class "Default")
      (node (ref "1_TX") (pin "1") (pinfunction "3_1") (pintype "passive"))
    )
    (net (code "49") (name "unconnected-(6-3-Pad1)") (class "Default")
      (node (ref "6") (pin "1") (pinfunction "3_1") (pintype "passive"))
    )
    (net (code "50") (name "unconnected-(7-3-Pad1)") (class "Default")
      (node (ref "7") (pin "1") (pinfunction "3_1") (pintype "passive"))
    )
    (net (code "51") (name "unconnected-(28-3-Pad1)") (class "Default")
      (node (ref "28") (pin "1") (pinfunction "3_1") (pintype "passive"))
    )
    (net (code "52") (name "unconnected-(29-3-Pad1)") (class "Default")
      (node (ref "29") (pin "1") (pinfunction "3_1") (pintype "passive"))
    )
    (net (code "53") (name "unconnected-(30-3-Pad1)") (class "Default")
      (node (ref "30") (pin "1") (pinfunction "3_1") (pintype "passive"))
    )
    (net (code "54") (name "unconnected-(31-3-Pad1)") (class "Default")
      (node (ref "31") (pin "1") (pinfunction "3_1") (pintype "passive"))
    )
    (net (code "55") (name "unconnected-(32-3-Pad1)") (class "Default")
      (node (ref "32") (pin "1") (pinfunction "3_1") (pintype "passive"))
    )
    (net (code "56") (name "unconnected-(33-3-Pad1)") (class "Default")
      (node (ref "33") (pin "1") (pinfunction "3_1") (pintype "passive"))
    )
    (net (code "57") (name "unconnected-(34-3-Pad1)") (class "Default")
      (node (ref "34") (pin "1") (pinfunction "3_1") (pintype "passive"))
    )
    (net (code "58") (name "unconnected-(35-3-Pad1)") (class "Default")
      (node (ref "35") (pin "1") (pinfunction "3_1") (pintype "passive"))
    )
    (net (code "59") (name "unconnected-(36-3-Pad1)") (class "Default")
      (node (ref "36") (pin "1") (pinfunction "3_1") (pintype "passive"))
    )
    (net (code "60") (name "unconnected-(37-3-Pad1)") (class "Default")
      (node (ref "37") (pin "1") (pinfunction "3_1") (pintype "passive"))
    )
    (net (code "61") (name "unconnected-(38-3-Pad1)") (class "Default")
      (node (ref "38") (pin "1") (pinfunction "3_1") (pintype "passive"))
    )
    (net (code "62") (name "unconnected-(39-3-Pad1)") (class "Default")
      (node (ref "39") (pin "1") (pinfunction "3_1") (pintype "passive"))
    )
    (net (code "63") (name "unconnected-(40-3-Pad1)") (class "Default")
      (node (ref "40") (pin "1") (pinfunction "3_1") (pintype "passive"))
    )
    (net (code "64") (name "unconnected-(41-3-Pad1)") (class "Default")
      (node (ref "41") (pin "1") (pinfunction "3_1") (pintype "passive"))
    )
    (net (code "65") (name "unconnected-(CV1_-3-Pad1)") (class "Default")
      (node (ref "CV1_") (pin "1") (pinfunction "3_1") (pintype "passive"))
    )
    (net (code "66") (name "unconnected-(CV6-3-Pad1)") (class "Default")
      (node (ref "CV6") (pin "1") (pinfunction "3_1") (pintype "passive"))
    )
    (net (code "67") (name "unconnected-(CV6_-3-Pad1)") (class "Default")
      (node (ref "CV6_") (pin "1") (pinfunction "3_1") (pintype "passive"))
    )
    (net (code "68") (name "unconnected-(CV7-3-Pad1)") (class "Default")
      (node (ref "CV7") (pin "1") (pinfunction "3_1") (pintype "passive"))
    )
    (net (code "69") (name "unconnected-(CV7_-3-Pad1)") (class "Default")
      (node (ref "CV7_") (pin "1") (pinfunction "3_1") (pintype "passive"))
    )
    (net (code "70") (name "unconnected-(CV8-3-Pad1)") (class "Default")
      (node (ref "CV8") (pin "1") (pinfunction "3_1") (pintype "passive"))
    )
    (net (code "71") (name "unconnected-(CV8_-3-Pad1)") (class "Default")
      (node (ref "CV8_") (pin "1") (pinfunction "3_1") (pintype "passive"))
    )
    (net (code "72") (name "unconnected-(CV9-3-Pad1)") (class "Default")
      (node (ref "CV9") (pin "1") (pinfunction "3_1") (pintype "passive"))
    )
    (net (code "73") (name "unconnected-(CV9_-3-Pad1)") (class "Default")
      (node (ref "CV9_") (pin "1") (pinfunction "3_1") (pintype "passive"))
    )
    (net (code "74") (name "unconnected-(CV10-3-Pad1)") (class "Default")
      (node (ref "CV10") (pin "1") (pinfunction "3_1") (pintype "passive"))
    )
    (net (code "75") (name "unconnected-(CV10_-3-Pad1)") (class "Default")
      (node (ref "CV10_") (pin "1") (pinfunction "3_1") (pintype "passive"))
    )
    (net (code "76") (name "unconnected-(CV11-3-Pad1)") (class "Default")
      (node (ref "CV11") (pin "1") (pinfunction "3_1") (pintype "passive"))
    )
    (net (code "77") (name "unconnected-(CV11_-3-Pad1)") (class "Default")
      (node (ref "CV11_") (pin "1") (pinfunction "3_1") (pintype "passive"))
    )
    (net (code "78") (name "unconnected-(CV12-3-Pad1)") (class "Default")
      (node (ref "CV12") (pin "1") (pinfunction "3_1") (pintype "passive"))
    )
    (net (code "79") (name "unconnected-(CV12_-3-Pad1)") (class "Default")
      (node (ref "CV12_") (pin "1") (pinfunction "3_1") (pintype "passive"))
    )
    (net (code "80") (name "unconnected-(IC1-INTB-Pad9)") (class "Default")
      (node (ref "IC1") (pin "9") (pinfunction "INTB_9") (pintype "input"))
    )
    (net (code "81") (name "unconnected-(IC1-SW6-Pad19)") (class "Default")
      (node (ref "IC1") (pin "19") (pinfunction "SW6_19") (pintype "output"))
    )
    (net (code "82") (name "unconnected-(IC1-SYNC-Pad5)") (class "Default")
      (node (ref "IC1") (pin "5") (pinfunction "SYNC_5") (pintype "input"))
    )
    (net (code "83") (name "unconnected-(IO1-3-Pad1)") (class "Default")
      (node (ref "IO1") (pin "1") (pinfunction "3_1") (pintype "passive"))
    )
    (net (code "84") (name "unconnected-(IO2-3-Pad1)") (class "Default")
      (node (ref "IO2") (pin "1") (pinfunction "3_1") (pintype "passive"))
    )
    (net (code "85") (name "unconnected-(IO3-3-Pad1)") (class "Default")
      (node (ref "IO3") (pin "1") (pinfunction "3_1") (pintype "passive"))
    )
    (net (code "86") (name "unconnected-(IO4-3-Pad1)") (class "Default")
      (node (ref "IO4") (pin "1") (pinfunction "3_1") (pintype "passive"))
    )
    (net (code "87") (name "unconnected-(IO5-3-Pad1)") (class "Default")
      (node (ref "IO5") (pin "1") (pinfunction "3_1") (pintype "passive"))
    )
    (net (code "88") (name "unconnected-(IO6-3-Pad1)") (class "Default")
      (node (ref "IO6") (pin "1") (pinfunction "3_1") (pintype "passive"))
    )
    (net (code "89") (name "unconnected-(IO7-3-Pad1)") (class "Default")
      (node (ref "IO7") (pin "1") (pinfunction "3_1") (pintype "passive"))
    )
    (net (code "90") (name "unconnected-(IO8-3-Pad1)") (class "Default")
      (node (ref "IO8") (pin "1") (pinfunction "3_1") (pintype "passive"))
    )
    (net (code "91") (name "unconnected-(IO9-3-Pad1)") (class "Default")
      (node (ref "IO9") (pin "1") (pinfunction "3_1") (pintype "passive"))
    )
    (net (code "92") (name "unconnected-(IO10-3-Pad1)") (class "Default")
      (node (ref "IO10") (pin "1") (pinfunction "3_1") (pintype "passive"))
    )
    (net (code "93") (name "unconnected-(IO11-3-Pad1)") (class "Default")
      (node (ref "IO11") (pin "1") (pinfunction "3_1") (pintype "passive"))
    )
    (net (code "94") (name "unconnected-(IO12-3-Pad1)") (class "Default")
      (node (ref "IO12") (pin "1") (pinfunction "3_1") (pintype "passive"))
    )
    (net (code "95") (name "unconnected-(IO13-3-Pad1)") (class "Default")
      (node (ref "IO13") (pin "1") (pinfunction "3_1") (pintype "passive"))
    )
    (net (code "96") (name "unconnected-(IO14-3-Pad1)") (class "Default")
      (node (ref "IO14") (pin "1") (pinfunction "3_1") (pintype "passive"))
    )
    (net (code "97") (name "unconnected-(IO15-3-Pad1)") (class "Default")
      (node (ref "IO15") (pin "1") (pinfunction "3_1") (pintype "passive"))
    )
    (net (code "98") (name "unconnected-(IO16-3-Pad1)") (class "Default")
      (node (ref "IO16") (pin "1") (pinfunction "3_1") (pintype "passive"))
    )
    (net (code "99") (name "unconnected-(OU1-3-PadP$2)") (class "Default")
      (node (ref "OU1") (pin "P$2") (pinfunction "3_P$2") (pintype "passive"))
    )
    (net (code "100") (name "unconnected-(OUT2-3-PadP$2)") (class "Default")
      (node (ref "OUT2") (pin "P$2") (pinfunction "3_P$2") (pintype "passive"))
    )
    (net (code "101") (name "unconnected-(OUT3-3-PadP$2)") (class "Default")
      (node (ref "OUT3") (pin "P$2") (pinfunction "3_P$2") (pintype "passive"))
    )
    (net (code "102") (name "unconnected-(OUT4-3-PadP$2)") (class "Default")
      (node (ref "OUT4") (pin "P$2") (pinfunction "3_P$2") (pintype "passive"))
    )
    (net (code "103") (name "unconnected-(OUT5-3-PadP$2)") (class "Default")
      (node (ref "OUT5") (pin "P$2") (pinfunction "3_P$2") (pintype "passive"))
    )
    (net (code "104") (name "unconnected-(OUT6-3-PadP$2)") (class "Default")
      (node (ref "OUT6") (pin "P$2") (pinfunction "3_P$2") (pintype "passive"))
    )
    (net (code "105") (name "unconnected-(OUT7-3-PadP$2)") (class "Default")
      (node (ref "OUT7") (pin "P$2") (pinfunction "3_P$2") (pintype "passive"))
    )
    (net (code "106") (name "unconnected-(OUT8-3-PadP$2)") (class "Default")
      (node (ref "OUT8") (pin "P$2") (pinfunction "3_P$2") (pintype "passive"))
    )
    (net (code "107") (name "unconnected-(TRIG_OUT-3-PadP$2)") (class "Default")
      (node (ref "TRIG_OUT") (pin "P$2") (pinfunction "3_P$2") (pintype "passive"))
    )
  )
)
